# untitled.net
KiCad netlist of a schematic drawn in EAGLE
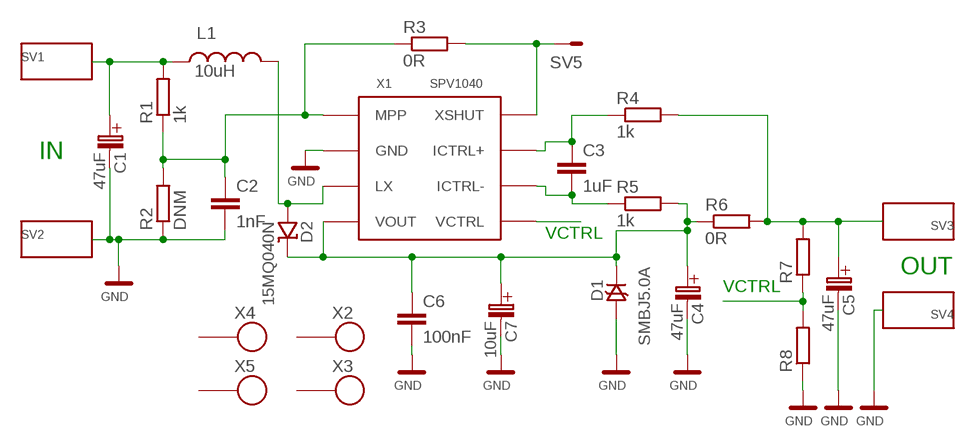
[diagram p0: schematic, sheet 1]

(export (version "E")
  (design (tool "Eeschema 10.0.6"))
  (components
    (comp (ref "C1") (value "47uF") (footprint "eagle-import:C") (libsource (lib "eagle-import") (part "C")))
    (comp (ref "C2")
      (value "1nF")
      (footprint "eagle-import:C0805")
      (libsource (lib "eagle-import") (part "C0805"))
    )
    (comp (ref "C3")
      (value "1uF")
      (footprint "eagle-import:C0805")
      (libsource (lib "eagle-import") (part "C0805"))
    )
    (comp (ref "C4") (value "47uF") (footprint "eagle-import:C") (libsource (lib "eagle-import") (part "C")))
    (comp (ref "C5") (value "47uF") (footprint "eagle-import:C") (libsource (lib "eagle-import") (part "C")))
    (comp (ref "C6")
      (value "100nF")
      (footprint "eagle-import:C0805")
      (libsource (lib "eagle-import") (part "C0805"))
    )
    (comp (ref "C7") (value "10uF") (footprint "eagle-import:B") (libsource (lib "eagle-import") (part "B")))
    (comp (ref "D1")
      (value "SMBJ5.0A")
      (footprint "eagle-import:SMB")
      (libsource (lib "eagle-import") (part "D-TRANSIL"))
    )
    (comp (ref "D2")
      (value "15MQ040N")
      (footprint "eagle-import:SMA")
      (libsource (lib "eagle-import") (part "D-SHOTKY-SMA"))
    )
    (comp (ref "L1")
      (value "10uH")
      (footprint "eagle-import:DE1205-10")
      (libsource (lib "eagle-import") (part "DE1205-10"))
    )
    (comp (ref "R1")
      (value "1k")
      (footprint "eagle-import:0805")
      (libsource (lib "eagle-import") (part "R0805"))
    )
    (comp (ref "R2")
      (value "DNM")
      (footprint "eagle-import:0805")
      (libsource (lib "eagle-import") (part "R0805"))
    )
    (comp (ref "R3")
      (value "0R")
      (footprint "eagle-import:1206")
      (libsource (lib "eagle-import") (part "R1206"))
    )
    (comp (ref "R4")
      (value "1k")
      (footprint "eagle-import:0805")
      (libsource (lib "eagle-import") (part "R0805"))
    )
    (comp (ref "R5")
      (value "1k")
      (footprint "eagle-import:0805")
      (libsource (lib "eagle-import") (part "R0805"))
    )
    (comp (ref "R6")
      (value "0R")
      (footprint "eagle-import:1206")
      (libsource (lib "eagle-import") (part "R1206"))
    )
    (comp (ref "R7")
      (value "R0805")
      (footprint "eagle-import:0805")
      (libsource (lib "eagle-import") (part "R0805"))
    )
    (comp (ref "R8")
      (value "R0805")
      (footprint "eagle-import:0805")
      (libsource (lib "eagle-import") (part "R0805"))
    )
    (comp (ref "SV1")
      (value "WAGO256")
      (footprint "eagle-import:WAGO256")
      (libsource (lib "eagle-import") (part "WAGO256"))
    )
    (comp (ref "SV2")
      (value "WAGO256")
      (footprint "eagle-import:WAGO256")
      (libsource (lib "eagle-import") (part "WAGO256"))
    )
    (comp (ref "SV3")
      (value "WAGO256")
      (footprint "eagle-import:WAGO256")
      (libsource (lib "eagle-import") (part "WAGO256"))
    )
    (comp (ref "SV4")
      (value "WAGO256")
      (footprint "eagle-import:WAGO256")
      (libsource (lib "eagle-import") (part "WAGO256"))
    )
    (comp (ref "SV5")
      (value "MA01-1")
      (footprint "eagle-import:MA01-1")
      (libsource (lib "eagle-import") (part "MA01-1"))
    )
    (comp (ref "X1")
      (value "SPV1040")
      (footprint "eagle-import:TSSOP8")
      (libsource (lib "eagle-import") (part "SPV1040"))
    )
    (comp (ref "X2")
      (value "SROUB3M")
      (footprint "eagle-import:SROUB3M")
      (libsource (lib "eagle-import") (part "SROUB3M"))
    )
    (comp (ref "X3")
      (value "SROUB3M")
      (footprint "eagle-import:SROUB3M")
      (libsource (lib "eagle-import") (part "SROUB3M"))
    )
    (comp (ref "X4")
      (value "SROUB3M")
      (footprint "eagle-import:SROUB3M")
      (libsource (lib "eagle-import") (part "SROUB3M"))
    )
    (comp (ref "X5")
      (value "SROUB3M")
      (footprint "eagle-import:SROUB3M")
      (libsource (lib "eagle-import") (part "SROUB3M"))
    )
  )
  (nets
    (net (code "1") (name "/VCTRL") (class "Default")
      (node (ref "R7") (pin "1") (pinfunction "1_1") (pintype "passive"))
      (node (ref "R8") (pin "2") (pinfunction "2_2") (pintype "passive"))
      (node (ref "X1") (pin "5") (pinfunction "VCTRL_5") (pintype "bidirectional"))
    )
    (net (code "2") (name "GND") (class "Default")
      (node (ref "C1") (pin "-") (pinfunction "C_EL-_-") (pintype "passive"))
      (node (ref "C2") (pin "2") (pinfunction "2_2") (pintype "passive"))
      (node (ref "C4") (pin "-") (pinfunction "C_EL-_-") (pintype "passive"))
      (node (ref "C5") (pin "-") (pinfunction "C_EL-_-") (pintype "passive"))
      (node (ref "C6") (pin "2") (pinfunction "2_2") (pintype "passive"))
      (node (ref "C7") (pin "-") (pinfunction "C_EL-_-") (pintype "passive"))
      (node (ref "D1") (pin "A") (pinfunction "A_A") (pintype "passive"))
      (node (ref "R2") (pin "1") (pinfunction "1_1") (pintype "passive"))
      (node (ref "R8") (pin "1") (pinfunction "1_1") (pintype "passive"))
      (node (ref "SV2") (pin "1") (pinfunction "P$1_1") (pintype "passive"))
      (node (ref "SV2") (pin "A1") (pinfunction "P$1_A1") (pintype "passive"))
      (node (ref "SV4") (pin "1") (pinfunction "P$1_1") (pintype "passive"))
      (node (ref "SV4") (pin "A1") (pinfunction "P$1_A1") (pintype "passive"))
      (node (ref "X1") (pin "2") (pinfunction "GND_2") (pintype "bidirectional"))
    )
    (net (code "3") (name "Net-(C1-C_EL+)") (class "Default")
      (node (ref "C1") (pin "+") (pinfunction "C_EL+_+") (pintype "passive"))
      (node (ref "L1") (pin "P$1") (pinfunction "1_P$1") (pintype "passive"))
      (node (ref "R1") (pin "2") (pinfunction "2_2") (pintype "passive"))
      (node (ref "SV1") (pin "1") (pinfunction "P$1_1") (pintype "passive"))
      (node (ref "SV1") (pin "A1") (pinfunction "P$1_A1") (pintype "passive"))
    )
    (net (code "4") (name "Net-(C4-C_EL+)") (class "Default")
      (node (ref "C4") (pin "+") (pinfunction "C_EL+_+") (pintype "passive"))
      (node (ref "C6") (pin "1") (pinfunction "1_1") (pintype "passive"))
      (node (ref "C7") (pin "+") (pinfunction "C_EL+_+") (pintype "passive"))
      (node (ref "D1") (pin "K") (pinfunction "K_K") (pintype "passive"))
      (node (ref "D2") (pin "K") (pinfunction "K_K") (pintype "passive"))
      (node (ref "R5") (pin "2") (pinfunction "2_2") (pintype "passive"))
      (node (ref "R6") (pin "1") (pinfunction "1_1") (pintype "passive"))
      (node (ref "X1") (pin "4") (pinfunction "VOUT_4") (pintype "bidirectional"))
    )
    (net (code "5") (name "Net-(C5-C_EL+)") (class "Default")
      (node (ref "C5") (pin "+") (pinfunction "C_EL+_+") (pintype "passive"))
      (node (ref "R4") (pin "2") (pinfunction "2_2") (pintype "passive"))
      (node (ref "R6") (pin "2") (pinfunction "2_2") (pintype "passive"))
      (node (ref "R7") (pin "2") (pinfunction "2_2") (pintype "passive"))
      (node (ref "SV3") (pin "1") (pinfunction "P$1_1") (pintype "passive"))
      (node (ref "SV3") (pin "A1") (pinfunction "P$1_A1") (pintype "passive"))
    )
    (net (code "6") (name "Net-(L1-2)") (class "Default")
      (node (ref "D2") (pin "A") (pinfunction "A_A") (pintype "passive"))
      (node (ref "L1") (pin "P$2") (pinfunction "2_P$2") (pintype "passive"))
      (node (ref "X1") (pin "3") (pinfunction "LX_3") (pintype "bidirectional"))
    )
    (net (code "7") (name "Net-(SV5-P$1)") (class "Default")
      (node (ref "R3") (pin "2") (pinfunction "2_2") (pintype "passive"))
      (node (ref "SV5") (pin "1") (pinfunction "P$1_1") (pintype "passive"))
      (node (ref "X1") (pin "8") (pinfunction "XSHUT_8") (pintype "bidirectional"))
    )
    (net (code "8") (name "Net-(X1-ICTRL+)") (class "Default")
      (node (ref "C3") (pin "1") (pinfunction "1_1") (pintype "passive"))
      (node (ref "R4") (pin "1") (pinfunction "1_1") (pintype "passive"))
      (node (ref "X1") (pin "7") (pinfunction "ICTRL+_7") (pintype "bidirectional"))
    )
    (net (code "9") (name "Net-(X1-ICTRL-)") (class "Default")
      (node (ref "C3") (pin "2") (pinfunction "2_2") (pintype "passive"))
      (node (ref "R5") (pin "1") (pinfunction "1_1") (pintype "passive"))
      (node (ref "X1") (pin "6") (pinfunction "ICTRL-_6") (pintype "bidirectional"))
    )
    (net (code "10") (name "Net-(X1-MPP)") (class "Default")
      (node (ref "C2") (pin "1") (pinfunction "1_1") (pintype "passive"))
      (node (ref "R1") (pin "1") (pinfunction "1_1") (pintype "passive"))
      (node (ref "R2") (pin "2") (pinfunction "2_2") (pintype "passive"))
      (node (ref "R3") (pin "1") (pinfunction "1_1") (pintype "passive"))
      (node (ref "X1") (pin "1") (pinfunction "MPP_1") (pintype "bidirectional"))
    )
    (net (code "11") (name "unconnected-(X2-PadP$1)") (class "Default")
      (node (ref "X2") (pin "P$1") (pinfunction "P$1_P$1") (pintype "bidirectional"))
    )
    (net (code "12") (name "unconnected-(X3-PadP$1)") (class "Default")
      (node (ref "X3") (pin "P$1") (pinfunction "P$1_P$1") (pintype "bidirectional"))
    )
    (net (code "13") (name "unconnected-(X4-PadP$1)") (class "Default")
      (node (ref "X4") (pin "P$1") (pinfunction "P$1_P$1") (pintype "bidirectional"))
    )
    (net (code "14") (name "unconnected-(X5-PadP$1)") (class "Default")
      (node (ref "X5") (pin "P$1") (pinfunction "P$1_P$1") (pintype "bidirectional"))
    )
  )
)
